# Placa_Pic16F628.net
KiCad netlist of a schematic drawn in EAGLE
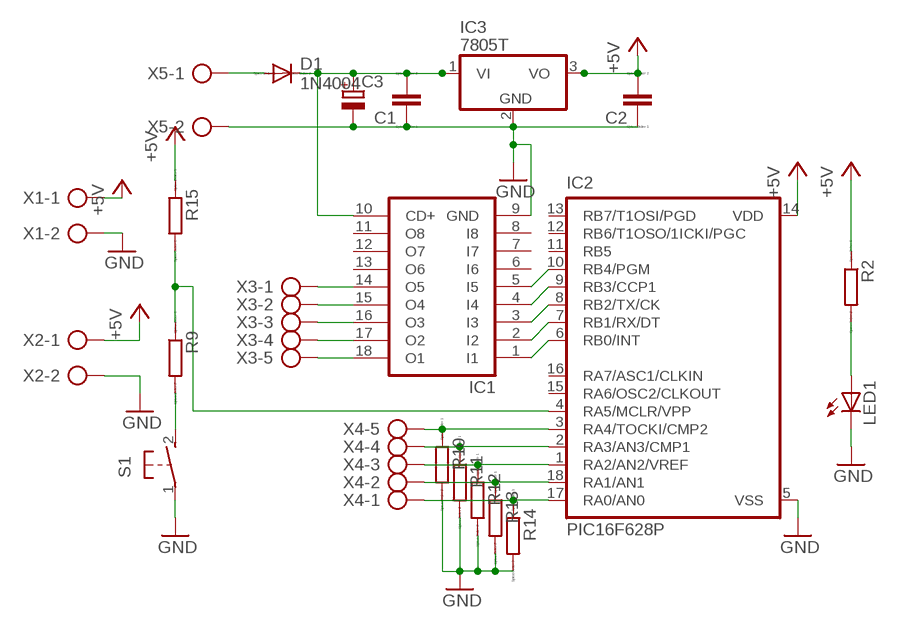
[diagram p0: schematic, sheet 1]

(export (version "E")
  (design (tool "Eeschema 10.0.6"))
  (components
    (comp (ref "C1")
      (value "C-EU050-030X075")
      (footprint "eagle-import:C050-030X075")
      (libsource (lib "eagle-import") (part "C-EU050-030X075"))
    )
    (comp (ref "C2")
      (value "C-EU050-030X075")
      (footprint "eagle-import:C050-030X075")
      (libsource (lib "eagle-import") (part "C-EU050-030X075"))
    )
    (comp (ref "C3")
      (value "CPOL-EUB45181B")
      (footprint "eagle-import:B45181B")
      (libsource (lib "eagle-import") (part "CPOL-EUB45181B"))
    )
    (comp (ref "D1")
      (value "1N4004")
      (footprint "eagle-import:DO41-10")
      (libsource (lib "eagle-import") (part "1N4004"))
    )
    (comp (ref "IC1")
      (value "ULN2803A")
      (footprint "eagle-import:DIL18")
      (libsource (lib "eagle-import") (part "ULN2803A"))
    )
    (comp (ref "IC2")
      (value "PIC16F628P")
      (footprint "eagle-import:DIL18")
      (fields (field (name "MF") "MICROCHIP") (field (name "MPN") "PIC16F628-20/P"))
      (libsource (lib "eagle-import") (part "PIC16F628P"))
    )
    (comp (ref "IC3")
      (value "7805T")
      (footprint "eagle-import:TO220H")
      (libsource (lib "eagle-import") (part "78T05"))
    )
    (comp (ref "LED1")
      (value "LED5MM")
      (footprint "eagle-import:LED5MM")
      (libsource (lib "eagle-import") (part "LED5MM"))
    )
    (comp (ref "R2")
      (value "R-EU_0207_12")
      (footprint "eagle-import:0207_12")
      (libsource (lib "eagle-import") (part "R-EU_0207_12"))
    )
    (comp (ref "R9")
      (value "R-EU_0207_12")
      (footprint "eagle-import:0207_12")
      (libsource (lib "eagle-import") (part "R-EU_0207_12"))
    )
    (comp (ref "R10")
      (value "R-EU_0207_12")
      (footprint "eagle-import:0207_12")
      (libsource (lib "eagle-import") (part "R-EU_0207_12"))
    )
    (comp (ref "R11")
      (value "R-EU_0207_12")
      (footprint "eagle-import:0207_12")
      (libsource (lib "eagle-import") (part "R-EU_0207_12"))
    )
    (comp (ref "R12")
      (value "R-EU_0207_12")
      (footprint "eagle-import:0207_12")
      (libsource (lib "eagle-import") (part "R-EU_0207_12"))
    )
    (comp (ref "R13")
      (value "R-EU_0207_12")
      (footprint "eagle-import:0207_12")
      (libsource (lib "eagle-import") (part "R-EU_0207_12"))
    )
    (comp (ref "R14")
      (value "R-EU_0207_12")
      (footprint "eagle-import:0207_12")
      (libsource (lib "eagle-import") (part "R-EU_0207_12"))
    )
    (comp (ref "R15")
      (value "R-EU_0207_12")
      (footprint "eagle-import:0207_12")
      (libsource (lib "eagle-import") (part "R-EU_0207_12"))
    )
    (comp (ref "S1")
      (value "31-XX")
      (footprint "eagle-import:B3F-31XX")
      (fields (field (name "MPN") "B3F-3100"))
      (libsource (lib "eagle-import") (part "31-XX"))
    )
    (comp (ref "X1")
      (value "AK300/2")
      (footprint "eagle-import:AK300_2")
      (libsource (lib "eagle-import") (part "AK300/2"))
    )
    (comp (ref "X2")
      (value "AK300/2")
      (footprint "eagle-import:AK300_2")
      (libsource (lib "eagle-import") (part "AK300/2"))
    )
    (comp (ref "X3")
      (value "AK300/5")
      (footprint "eagle-import:AK300_5")
      (libsource (lib "eagle-import") (part "AK300/5"))
    )
    (comp (ref "X4")
      (value "AK300/5")
      (footprint "eagle-import:AK300_5")
      (libsource (lib "eagle-import") (part "AK300/5"))
    )
    (comp (ref "X5")
      (value "AK300/2")
      (footprint "eagle-import:AK300_2")
      (libsource (lib "eagle-import") (part "AK300/2"))
    )
  )
  (nets
    (net (code "1") (name "+5V") (class "Default")
      (node (ref "C2") (pin "2") (pinfunction "2_2") (pintype "passive"))
      (node (ref "IC2") (pin "14") (pinfunction "VDD_14") (pintype "power_in"))
      (node (ref "IC3") (pin "3") (pinfunction "VO_3") (pintype "passive"))
      (node (ref "R15") (pin "1") (pinfunction "1_1") (pintype "passive"))
      (node (ref "R2") (pin "1") (pinfunction "1_1") (pintype "passive"))
      (node (ref "X1") (pin "1") (pinfunction "KL_1") (pintype "passive"))
      (node (ref "X2") (pin "1") (pinfunction "KL_1") (pintype "passive"))
    )
    (net (code "2") (name "GND") (class "Default")
      (node (ref "C1") (pin "1") (pinfunction "1_1") (pintype "passive"))
      (node (ref "C2") (pin "1") (pinfunction "1_1") (pintype "passive"))
      (node (ref "C3") (pin "-") (pinfunction "-_-") (pintype "passive"))
      (node (ref "IC1") (pin "9") (pinfunction "GND_9") (pintype "power_in"))
      (node (ref "IC2") (pin "5") (pinfunction "VSS_5") (pintype "power_in"))
      (node (ref "IC3") (pin "2") (pinfunction "GND_2") (pintype "passive"))
      (node (ref "LED1") (pin "K") (pinfunction "C_K") (pintype "passive"))
      (node (ref "R10") (pin "2") (pinfunction "2_2") (pintype "passive"))
      (node (ref "R11") (pin "2") (pinfunction "2_2") (pintype "passive"))
      (node (ref "R12") (pin "2") (pinfunction "2_2") (pintype "passive"))
      (node (ref "R13") (pin "2") (pinfunction "2_2") (pintype "passive"))
      (node (ref "R14") (pin "2") (pinfunction "2_2") (pintype "passive"))
      (node (ref "S1") (pin "1") (pinfunction "P_1") (pintype "passive"))
      (node (ref "X1") (pin "2") (pinfunction "KL_2") (pintype "passive"))
      (node (ref "X2") (pin "2") (pinfunction "KL_2") (pintype "passive"))
      (node (ref "X5") (pin "2") (pinfunction "KL_2") (pintype "passive"))
    )
    (net (code "3") (name "Net-(IC1-CD+)") (class "Default")
      (node (ref "C1") (pin "2") (pinfunction "2_2") (pintype "passive"))
      (node (ref "C3") (pin "+") (pinfunction "+_+") (pintype "passive"))
      (node (ref "D1") (pin "C") (pinfunction "C_C") (pintype "passive"))
      (node (ref "IC1") (pin "10") (pinfunction "CD+_10") (pintype "passive"))
      (node (ref "IC3") (pin "1") (pinfunction "VI_1") (pintype "input"))
    )
    (net (code "4") (name "Net-(IC1-I1)") (class "Default")
      (node (ref "IC1") (pin "1") (pinfunction "I1_1") (pintype "input"))
      (node (ref "IC2") (pin "6") (pinfunction "RB0/INT_6") (pintype "bidirectional"))
    )
    (net (code "5") (name "Net-(IC1-I2)") (class "Default")
      (node (ref "IC1") (pin "2") (pinfunction "I2_2") (pintype "input"))
      (node (ref "IC2") (pin "7") (pinfunction "RB1/RX/DT_7") (pintype "bidirectional"))
    )
    (net (code "6") (name "Net-(IC1-I3)") (class "Default")
      (node (ref "IC1") (pin "3") (pinfunction "I3_3") (pintype "input"))
      (node (ref "IC2") (pin "8") (pinfunction "RB2/TX/CK_8") (pintype "bidirectional"))
    )
    (net (code "7") (name "Net-(IC1-I4)") (class "Default")
      (node (ref "IC1") (pin "4") (pinfunction "I4_4") (pintype "input"))
      (node (ref "IC2") (pin "9") (pinfunction "RB3/CCP1_9") (pintype "bidirectional"))
    )
    (net (code "8") (name "Net-(IC1-I5)") (class "Default")
      (node (ref "IC1") (pin "5") (pinfunction "I5_5") (pintype "input"))
      (node (ref "IC2") (pin "10") (pinfunction "RB4/PGM_10") (pintype "bidirectional"))
    )
    (net (code "9") (name "Net-(IC1-O1)") (class "Default")
      (node (ref "IC1") (pin "18") (pinfunction "O1_18") (pintype "open_collector"))
      (node (ref "X3") (pin "5") (pinfunction "KL_5") (pintype "passive"))
    )
    (net (code "10") (name "Net-(IC1-O2)") (class "Default")
      (node (ref "IC1") (pin "17") (pinfunction "O2_17") (pintype "open_collector"))
      (node (ref "X3") (pin "4") (pinfunction "KL_4") (pintype "passive"))
    )
    (net (code "11") (name "Net-(IC1-O3)") (class "Default")
      (node (ref "IC1") (pin "16") (pinfunction "O3_16") (pintype "open_collector"))
      (node (ref "X3") (pin "3") (pinfunction "KL_3") (pintype "passive"))
    )
    (net (code "12") (name "Net-(IC1-O4)") (class "Default")
      (node (ref "IC1") (pin "15") (pinfunction "O4_15") (pintype "open_collector"))
      (node (ref "X3") (pin "2") (pinfunction "KL_2") (pintype "passive"))
    )
    (net (code "13") (name "Net-(IC1-O5)") (class "Default")
      (node (ref "IC1") (pin "14") (pinfunction "O5_14") (pintype "open_collector"))
      (node (ref "X3") (pin "1") (pinfunction "KL_1") (pintype "passive"))
    )
    (net (code "14") (name "Net-(IC2-RA0{slash}AN0)") (class "Default")
      (node (ref "IC2") (pin "17") (pinfunction "RA0/AN0_17") (pintype "bidirectional"))
      (node (ref "R14") (pin "1") (pinfunction "1_1") (pintype "passive"))
      (node (ref "X4") (pin "1") (pinfunction "KL_1") (pintype "passive"))
    )
    (net (code "15") (name "Net-(IC2-RA1{slash}AN1)") (class "Default")
      (node (ref "IC2") (pin "18") (pinfunction "RA1/AN1_18") (pintype "bidirectional"))
      (node (ref "R13") (pin "1") (pinfunction "1_1") (pintype "passive"))
      (node (ref "X4") (pin "2") (pinfunction "KL_2") (pintype "passive"))
    )
    (net (code "16") (name "Net-(IC2-RA2{slash}AN2{slash}VREF)") (class "Default")
      (node (ref "IC2") (pin "1") (pinfunction "RA2/AN2/VREF_1") (pintype "bidirectional"))
      (node (ref "R12") (pin "1") (pinfunction "1_1") (pintype "passive"))
      (node (ref "X4") (pin "3") (pinfunction "KL_3") (pintype "passive"))
    )
    (net (code "17") (name "Net-(IC2-RA3{slash}AN3{slash}CMP1)") (class "Default")
      (node (ref "IC2") (pin "2") (pinfunction "RA3/AN3/CMP1_2") (pintype "bidirectional"))
      (node (ref "R11") (pin "1") (pinfunction "1_1") (pintype "passive"))
      (node (ref "X4") (pin "4") (pinfunction "KL_4") (pintype "passive"))
    )
    (net (code "18") (name "Net-(IC2-RA4{slash}TOCKI{slash}CMP2)") (class "Default")
      (node (ref "IC2") (pin "3") (pinfunction "RA4/TOCKI/CMP2_3") (pintype "bidirectional"))
      (node (ref "R10") (pin "1") (pinfunction "1_1") (pintype "passive"))
      (node (ref "X4") (pin "5") (pinfunction "KL_5") (pintype "passive"))
    )
    (net (code "19") (name "Net-(IC2-RA5{slash}MCLR{slash}VPP)") (class "Default")
      (node (ref "IC2") (pin "4") (pinfunction "RA5/MCLR/VPP_4") (pintype "input"))
      (node (ref "R15") (pin "2") (pinfunction "2_2") (pintype "passive"))
      (node (ref "R9") (pin "1") (pinfunction "1_1") (pintype "passive"))
    )
    (net (code "20") (name "Net-(LED1-PadA)") (class "Default")
      (node (ref "LED1") (pin "A") (pinfunction "A_A") (pintype "passive"))
      (node (ref "R2") (pin "2") (pinfunction "2_2") (pintype "passive"))
    )
    (net (code "21") (name "Net-(S1-S)") (class "Default")
      (node (ref "R9") (pin "2") (pinfunction "2_2") (pintype "passive"))
      (node (ref "S1") (pin "2") (pinfunction "S_2") (pintype "passive"))
    )
    (net (code "22") (name "Net-(X5A-KL)") (class "Default")
      (node (ref "D1") (pin "A") (pinfunction "A_A") (pintype "passive"))
      (node (ref "X5") (pin "1") (pinfunction "KL_1") (pintype "passive"))
    )
    (net (code "23") (name "unconnected-(IC1-I6-Pad6)") (class "Default")
      (node (ref "IC1") (pin "6") (pinfunction "I6_6") (pintype "input"))
    )
    (net (code "24") (name "unconnected-(IC1-I7-Pad7)") (class "Default")
      (node (ref "IC1") (pin "7") (pinfunction "I7_7") (pintype "input"))
    )
    (net (code "25") (name "unconnected-(IC1-I8-Pad8)") (class "Default")
      (node (ref "IC1") (pin "8") (pinfunction "I8_8") (pintype "input"))
    )
    (net (code "26") (name "unconnected-(IC1-O6-Pad13)") (class "Default")
      (node (ref "IC1") (pin "13") (pinfunction "O6_13") (pintype "open_collector"))
    )
    (net (code "27") (name "unconnected-(IC1-O7-Pad12)") (class "Default")
      (node (ref "IC1") (pin "12") (pinfunction "O7_12") (pintype "open_collector"))
    )
    (net (code "28") (name "unconnected-(IC1-O8-Pad11)") (class "Default")
      (node (ref "IC1") (pin "11") (pinfunction "O8_11") (pintype "open_collector"))
    )
    (net (code "29") (name "unconnected-(IC2-RA6{slash}OSC2{slash}CLKOUT-Pad15)") (class "Default")
      (node (ref "IC2") (pin "15") (pinfunction "RA6/OSC2/CLKOUT_15") (pintype "bidirectional"))
    )
    (net (code "30") (name "unconnected-(IC2-RA7{slash}ASC1{slash}CLKIN-Pad16)") (class "Default")
      (node (ref "IC2") (pin "16") (pinfunction "RA7/ASC1/CLKIN_16") (pintype "bidirectional"))
    )
    (net (code "31") (name "unconnected-(IC2-RB5-Pad11)") (class "Default")
      (node (ref "IC2") (pin "11") (pinfunction "RB5_11") (pintype "bidirectional"))
    )
    (net (code "32") (name "unconnected-(IC2-RB6{slash}T1OSO{slash}1ICKI{slash}PGC-Pad12)") (class "Default")
      (node (ref "IC2") (pin "12") (pinfunction "RB6/T1OSO/1ICKI/PGC_12") (pintype "bidirectional"))
    )
    (net (code "33") (name "unconnected-(IC2-RB7{slash}T1OSI{slash}PGD-Pad13)") (class "Default")
      (node (ref "IC2") (pin "13") (pinfunction "RB7/T1OSI/PGD_13") (pintype "bidirectional"))
    )
  )
)
